# PCB.net
KiCad netlist of a schematic drawn in EAGLE
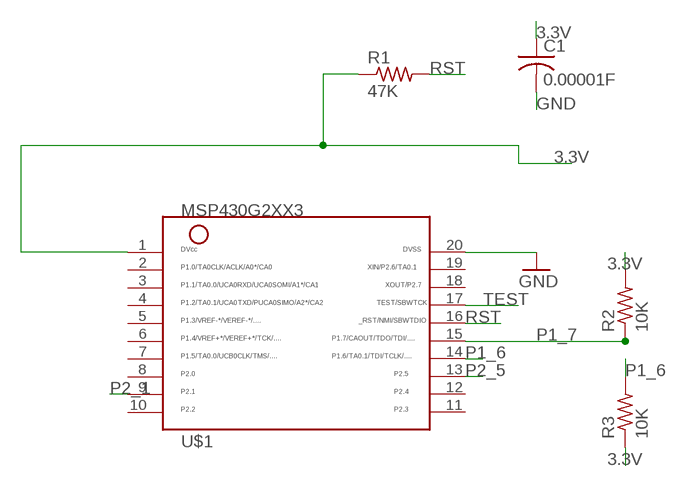
[diagram p0: schematic, sheet 1]

(export (version "E")
  (design (tool "Eeschema 10.0.6"))
  (components
    (comp (ref "C1")
      (value "0.00001F")
      (footprint "eagle-import:C1206")
      (libsource (lib "eagle-import") (part "C-USC1206"))
    )
    (comp (ref "R1")
      (value "47K")
      (footprint "eagle-import:R1206")
      (libsource (lib "eagle-import") (part "R-US_R1206"))
    )
    (comp (ref "R2")
      (value "10K")
      (footprint "eagle-import:R1206")
      (libsource (lib "eagle-import") (part "R-US_R1206"))
    )
    (comp (ref "R3")
      (value "10K")
      (footprint "eagle-import:R1206")
      (libsource (lib "eagle-import") (part "R-US_R1206"))
    )
    (comp (ref "U$1")
      (value "MSP430G2XX3TSSOP")
      (footprint "eagle-import:PW20")
      (libsource (lib "eagle-import") (part "MSP430G2XX3TSSOP"))
    )
  )
  (nets
    (net (code "1") (name "/3.3V") (class "Default")
      (node (ref "C1") (pin "1") (pinfunction "1_1") (pintype "passive"))
      (node (ref "R1") (pin "1") (pinfunction "1_1") (pintype "passive"))
      (node (ref "R2") (pin "2") (pinfunction "2_2") (pintype "passive"))
      (node (ref "R3") (pin "1") (pinfunction "1_1") (pintype "passive"))
      (node (ref "U$1") (pin "1") (pinfunction "1_1") (pintype "bidirectional"))
    )
    (net (code "2") (name "/P1_6") (class "Default")
      (node (ref "R3") (pin "2") (pinfunction "2_2") (pintype "passive"))
      (node (ref "U$1") (pin "14") (pinfunction "14_14") (pintype "bidirectional"))
    )
    (net (code "3") (name "/P1_7") (class "Default")
      (node (ref "R2") (pin "1") (pinfunction "1_1") (pintype "passive"))
      (node (ref "U$1") (pin "15") (pinfunction "15_15") (pintype "bidirectional"))
    )
    (net (code "4") (name "/P2_1") (class "Default")
      (node (ref "U$1") (pin "9") (pinfunction "9_9") (pintype "bidirectional"))
    )
    (net (code "5") (name "/P2_5") (class "Default")
      (node (ref "U$1") (pin "13") (pinfunction "13_13") (pintype "bidirectional"))
    )
    (net (code "6") (name "/RST") (class "Default")
      (node (ref "R1") (pin "2") (pinfunction "2_2") (pintype "passive"))
      (node (ref "U$1") (pin "16") (pinfunction "16_16") (pintype "bidirectional"))
    )
    (net (code "7") (name "/TEST") (class "Default")
      (node (ref "U$1") (pin "17") (pinfunction "17_17") (pintype "bidirectional"))
    )
    (net (code "8") (name "GND") (class "Default")
      (node (ref "C1") (pin "2") (pinfunction "2_2") (pintype "passive"))
      (node (ref "U$1") (pin "20") (pinfunction "20_20") (pintype "bidirectional"))
    )
    (net (code "9") (name "unconnected-(U$1-Pad2)") (class "Default")
      (node (ref "U$1") (pin "2") (pinfunction "2_2") (pintype "bidirectional"))
    )
    (net (code "10") (name "unconnected-(U$1-Pad3)") (class "Default")
      (node (ref "U$1") (pin "3") (pinfunction "3_3") (pintype "bidirectional"))
    )
    (net (code "11") (name "unconnected-(U$1-Pad4)") (class "Default")
      (node (ref "U$1") (pin "4") (pinfunction "4_4") (pintype "bidirectional"))
    )
    (net (code "12") (name "unconnected-(U$1-Pad5)") (class "Default")
      (node (ref "U$1") (pin "5") (pinfunction "5_5") (pintype "bidirectional"))
    )
    (net (code "13") (name "unconnected-(U$1-Pad6)") (class "Default")
      (node (ref "U$1") (pin "6") (pinfunction "6_6") (pintype "bidirectional"))
    )
    (net (code "14") (name "unconnected-(U$1-Pad7)") (class "Default")
      (node (ref "U$1") (pin "7") (pinfunction "7_7") (pintype "bidirectional"))
    )
    (net (code "15") (name "unconnected-(U$1-Pad8)") (class "Default")
      (node (ref "U$1") (pin "8") (pinfunction "8_8") (pintype "bidirectional"))
    )
    (net (code "16") (name "unconnected-(U$1-Pad10)") (class "Default")
      (node (ref "U$1") (pin "10") (pinfunction "10_10") (pintype "bidirectional"))
    )
    (net (code "17") (name "unconnected-(U$1-Pad11)") (class "Default")
      (node (ref "U$1") (pin "11") (pinfunction "11_11") (pintype "bidirectional"))
    )
    (net (code "18") (name "unconnected-(U$1-Pad12)") (class "Default")
      (node (ref "U$1") (pin "12") (pinfunction "12_12") (pintype "bidirectional"))
    )
    (net (code "19") (name "unconnected-(U$1-Pad18)") (class "Default")
      (node (ref "U$1") (pin "18") (pinfunction "18_18") (pintype "bidirectional"))
    )
    (net (code "20") (name "unconnected-(U$1-Pad19)") (class "Default")
      (node (ref "U$1") (pin "19") (pinfunction "19_19") (pintype "bidirectional"))
    )
  )
)
